# PowerStage.net
KiCad netlist of a schematic drawn in EAGLE
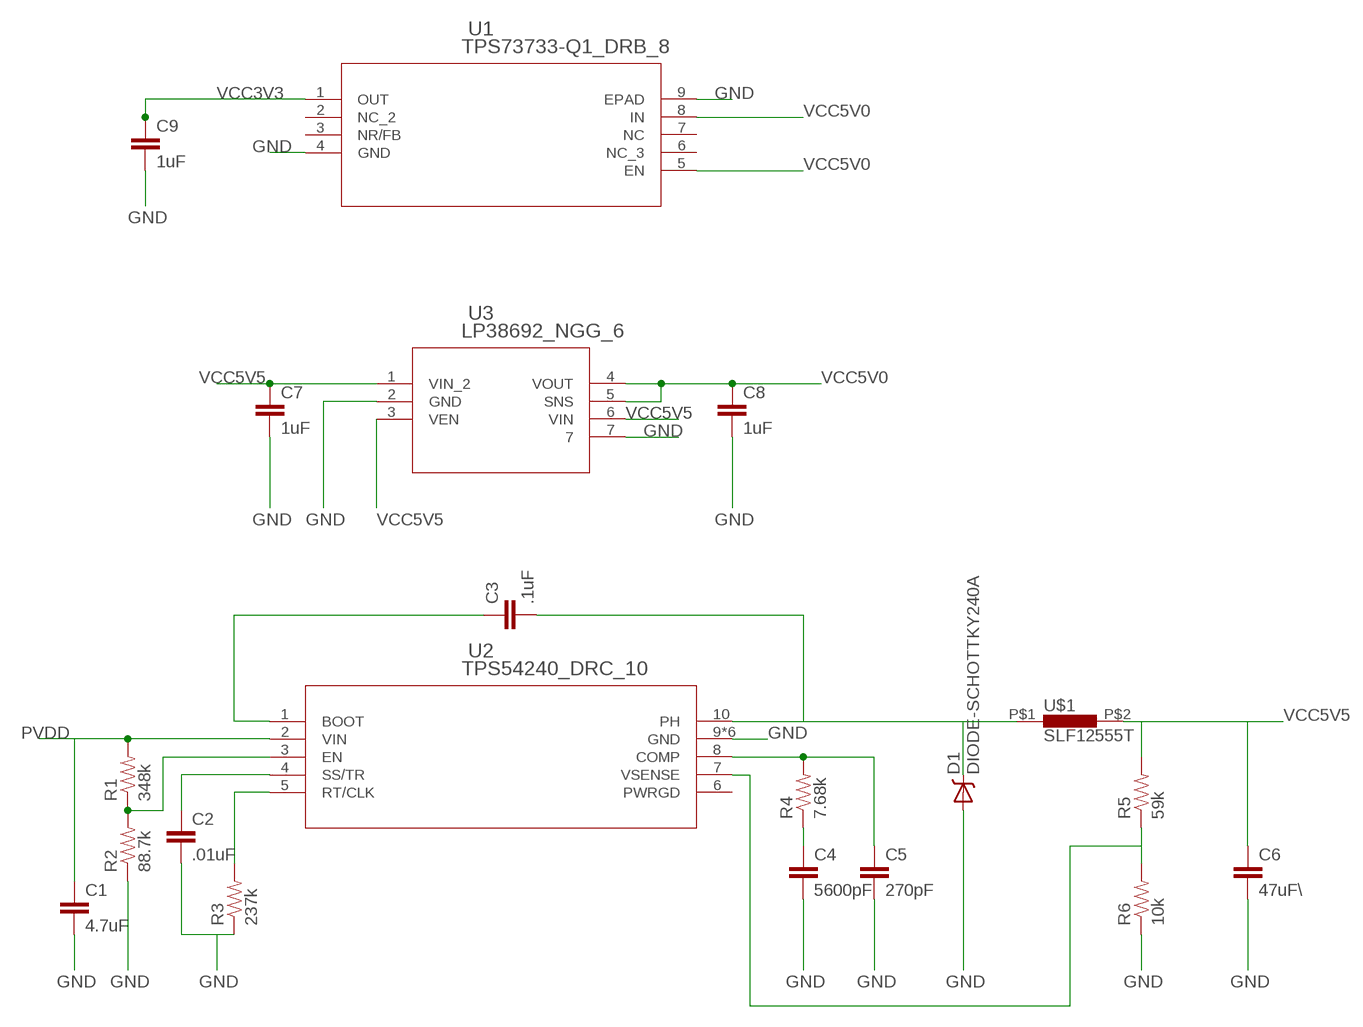
[diagram p0: schematic, sheet 1]

(export (version "E")
  (design (tool "Eeschema 10.0.6"))
  (components
    (comp (ref "C1")
      (value "4.7uF")
      (footprint "eagle-import:1210")
      (libsource (lib "eagle-import") (part "CAP1210"))
    )
    (comp (ref "C2")
      (value ".01uF")
      (footprint "eagle-import:0805")
      (libsource (lib "eagle-import") (part "CAP0805"))
    )
    (comp (ref "C3")
      (value ".1uF")
      (footprint "eagle-import:0805")
      (libsource (lib "eagle-import") (part "CAP0805"))
    )
    (comp (ref "C4")
      (value "5600pF")
      (footprint "eagle-import:0805")
      (libsource (lib "eagle-import") (part "CAP0805"))
    )
    (comp (ref "C5")
      (value "270pF")
      (footprint "eagle-import:0805")
      (libsource (lib "eagle-import") (part "CAP0805"))
    )
    (comp (ref "C6")
      (value "47uF\\")
      (footprint "eagle-import:C2220K")
      (libsource (lib "eagle-import") (part "CAP"))
    )
    (comp (ref "C7")
      (value "1uF")
      (footprint "eagle-import:0805")
      (libsource (lib "eagle-import") (part "CAP0805"))
    )
    (comp (ref "C8")
      (value "1uF")
      (footprint "eagle-import:0805")
      (libsource (lib "eagle-import") (part "CAP0805"))
    )
    (comp (ref "C9")
      (value "1uF")
      (footprint "eagle-import:0805")
      (libsource (lib "eagle-import") (part "CAP0805"))
    )
    (comp (ref "D1")
      (value "DIODE-SCHOTTKY240A")
      (footprint "eagle-import:SMA-DIODE-B240A")
      (libsource (lib "eagle-import") (part "DIODE-SCHOTTKY240A"))
    )
    (comp (ref "R1")
      (value "348k")
      (footprint "eagle-import:0805")
      (libsource (lib "eagle-import") (part "RESISTOR0805-RES"))
    )
    (comp (ref "R2")
      (value "88.7k")
      (footprint "eagle-import:0805")
      (libsource (lib "eagle-import") (part "RESISTOR0805-RES"))
    )
    (comp (ref "R3")
      (value "237k")
      (footprint "eagle-import:0805")
      (libsource (lib "eagle-import") (part "RESISTOR0805-RES"))
    )
    (comp (ref "R4")
      (value "7.68k")
      (footprint "eagle-import:0805")
      (libsource (lib "eagle-import") (part "RESISTOR0805-RES"))
    )
    (comp (ref "R5")
      (value "59k")
      (footprint "eagle-import:0805")
      (libsource (lib "eagle-import") (part "RESISTOR0805-RES"))
    )
    (comp (ref "R6")
      (value "10k")
      (footprint "eagle-import:0805")
      (libsource (lib "eagle-import") (part "RESISTOR0805-RES"))
    )
    (comp (ref "U$1")
      (value "SLF12555T")
      (footprint "eagle-import:SLF12555")
      (libsource (lib "eagle-import") (part "SLF12555T"))
    )
    (comp (ref "U1")
      (value "TPS73733-Q1_DRB_8")
      (footprint "eagle-import:DRB8_1P75X1P5")
      (fields
        (field (name "GENERIC_PART_NUMBER") "TPS73733-Q1")
        (field (name "MANUFACTURER") "Texas Instruments")
        (field (name "MANUFACTURER_PART_NUMBER") "tps73733-q1_drb_8")
      )
      (libsource (lib "eagle-import") (part "TPS73733-Q1_DRB_8"))
    )
    (comp (ref "U2")
      (value "TPS54240_DRC_10")
      (footprint "eagle-import:DRC10_2P4X1P65")
      (fields
        (field (name "GENERIC_PART_NUMBER") "TPS54240")
        (field (name "MANUFACTURER") "Texas Instruments")
        (field (name "MANUFACTURER_PART_NUMBER") "tps54240_drc_10")
      )
      (libsource (lib "eagle-import") (part "TPS54240_DRC_10"))
    )
    (comp (ref "U3")
      (value "LP38692_NGG_6")
      (footprint "eagle-import:SDE06A")
      (fields (field (name "PARTNUMBER") "LP38692SD-18"))
      (libsource (lib "eagle-import") (part "LP38692_NGG_6"))
    )
  )
  (nets
    (net (code "1") (name "/GND") (class "Default")
      (node (ref "C1") (pin "2") (pinfunction "2_2") (pintype "passive"))
      (node (ref "C2") (pin "2") (pinfunction "2_2") (pintype "passive"))
      (node (ref "C4") (pin "2") (pinfunction "2_2") (pintype "passive"))
      (node (ref "C5") (pin "2") (pinfunction "2_2") (pintype "passive"))
      (node (ref "C6") (pin "2") (pinfunction "2_2") (pintype "passive"))
      (node (ref "C7") (pin "2") (pinfunction "2_2") (pintype "passive"))
      (node (ref "C8") (pin "2") (pinfunction "2_2") (pintype "passive"))
      (node (ref "C9") (pin "2") (pinfunction "2_2") (pintype "passive"))
      (node (ref "D1") (pin "A") (pinfunction "A_A") (pintype "passive"))
      (node (ref "R2") (pin "1") (pinfunction "1_1") (pintype "passive"))
      (node (ref "R3") (pin "1") (pinfunction "1_1") (pintype "passive"))
      (node (ref "R6") (pin "1") (pinfunction "1_1") (pintype "passive"))
      (node (ref "U1") (pin "4") (pinfunction "GND_4") (pintype "power_in"))
      (node (ref "U1") (pin "9") (pinfunction "EPAD_9") (pintype "passive"))
      (node (ref "U2") (pin "9") (pinfunction "GND_9") (pintype "power_in"))
      (node (ref "U2") (pin "P$1") (pinfunction "GND_P$1") (pintype "power_in"))
      (node (ref "U2") (pin "P$2") (pinfunction "GND_P$2") (pintype "power_in"))
      (node (ref "U2") (pin "P$3") (pinfunction "GND_P$3") (pintype "power_in"))
      (node (ref "U2") (pin "P$4") (pinfunction "GND_P$4") (pintype "power_in"))
      (node (ref "U2") (pin "P$5") (pinfunction "GND_P$5") (pintype "power_in"))
      (node (ref "U3") (pin "2") (pinfunction "GND_2") (pintype "passive"))
      (node (ref "U3") (pin "7") (pinfunction "7_7") (pintype "passive"))
    )
    (net (code "2") (name "/PVDD") (class "Default")
      (node (ref "C1") (pin "1") (pinfunction "1_1") (pintype "passive"))
      (node (ref "R1") (pin "2") (pinfunction "2_2") (pintype "passive"))
      (node (ref "U2") (pin "2") (pinfunction "VIN_2") (pintype "input"))
    )
    (net (code "3") (name "/VCC3V3") (class "Default")
      (node (ref "C9") (pin "1") (pinfunction "1_1") (pintype "passive"))
      (node (ref "U1") (pin "1") (pinfunction "OUT_1") (pintype "output"))
    )
    (net (code "4") (name "/VCC5V0") (class "Default")
      (node (ref "C8") (pin "1") (pinfunction "1_1") (pintype "passive"))
      (node (ref "U1") (pin "5") (pinfunction "EN_5") (pintype "passive"))
      (node (ref "U1") (pin "8") (pinfunction "IN_8") (pintype "input"))
      (node (ref "U3") (pin "4") (pinfunction "VOUT_4") (pintype "output"))
      (node (ref "U3") (pin "5") (pinfunction "SNS_5") (pintype "passive"))
    )
    (net (code "5") (name "/VCC5V5") (class "Default")
      (node (ref "C6") (pin "1") (pinfunction "1_1") (pintype "passive"))
      (node (ref "C7") (pin "1") (pinfunction "1_1") (pintype "passive"))
      (node (ref "R5") (pin "2") (pinfunction "2_2") (pintype "passive"))
      (node (ref "U$1") (pin "P$2") (pinfunction "2_P$2") (pintype "passive"))
      (node (ref "U3") (pin "1") (pinfunction "VIN_2_1") (pintype "input"))
      (node (ref "U3") (pin "3") (pinfunction "VEN_3") (pintype "passive"))
      (node (ref "U3") (pin "6") (pinfunction "VIN_6") (pintype "input"))
    )
    (net (code "6") (name "Net-(C4-Pad1)") (class "Default")
      (node (ref "C4") (pin "1") (pinfunction "1_1") (pintype "passive"))
      (node (ref "R4") (pin "1") (pinfunction "1_1") (pintype "passive"))
    )
    (net (code "7") (name "Net-(U$1-1)") (class "Default")
      (node (ref "C3") (pin "2") (pinfunction "2_2") (pintype "passive"))
      (node (ref "D1") (pin "C") (pinfunction "C_C") (pintype "passive"))
      (node (ref "U$1") (pin "P$1") (pinfunction "1_P$1") (pintype "passive"))
      (node (ref "U2") (pin "10") (pinfunction "PH_10") (pintype "input"))
    )
    (net (code "8") (name "Net-(U2-BOOT)") (class "Default")
      (node (ref "C3") (pin "1") (pinfunction "1_1") (pintype "passive"))
      (node (ref "U2") (pin "1") (pinfunction "BOOT_1") (pintype "output"))
    )
    (net (code "9") (name "Net-(U2-COMP)") (class "Default")
      (node (ref "C5") (pin "1") (pinfunction "1_1") (pintype "passive"))
      (node (ref "R4") (pin "2") (pinfunction "2_2") (pintype "passive"))
      (node (ref "U2") (pin "8") (pinfunction "COMP_8") (pintype "output"))
    )
    (net (code "10") (name "Net-(U2-EN)") (class "Default")
      (node (ref "R1") (pin "1") (pinfunction "1_1") (pintype "passive"))
      (node (ref "R2") (pin "2") (pinfunction "2_2") (pintype "passive"))
      (node (ref "U2") (pin "3") (pinfunction "EN_3") (pintype "input"))
    )
    (net (code "11") (name "Net-(U2-RT{slash}CLK)") (class "Default")
      (node (ref "R3") (pin "2") (pinfunction "2_2") (pintype "passive"))
      (node (ref "U2") (pin "5") (pinfunction "RT/CLK_5") (pintype "input"))
    )
    (net (code "12") (name "Net-(U2-SS{slash}TR)") (class "Default")
      (node (ref "C2") (pin "1") (pinfunction "1_1") (pintype "passive"))
      (node (ref "U2") (pin "4") (pinfunction "SS/TR_4") (pintype "input"))
    )
    (net (code "13") (name "Net-(U2-VSENSE)") (class "Default")
      (node (ref "R5") (pin "1") (pinfunction "1_1") (pintype "passive"))
      (node (ref "R6") (pin "2") (pinfunction "2_2") (pintype "passive"))
      (node (ref "U2") (pin "7") (pinfunction "VSENSE_7") (pintype "input"))
    )
    (net (code "14") (name "unconnected-(U1-NC-Pad7)") (class "Default")
      (node (ref "U1") (pin "7") (pinfunction "NC_7") (pintype "passive"))
    )
    (net (code "15") (name "unconnected-(U1-NC_2-Pad2)") (class "Default")
      (node (ref "U1") (pin "2") (pinfunction "NC_2_2") (pintype "passive"))
    )
    (net (code "16") (name "unconnected-(U1-NC_3-Pad6)") (class "Default")
      (node (ref "U1") (pin "6") (pinfunction "NC_3_6") (pintype "passive"))
    )
    (net (code "17") (name "unconnected-(U1-NR{slash}FB-Pad3)") (class "Default")
      (node (ref "U1") (pin "3") (pinfunction "NR/FB_3") (pintype "bidirectional"))
    )
    (net (code "18") (name "unconnected-(U2-PWRGD-Pad6)") (class "Default")
      (node (ref "U2") (pin "6") (pinfunction "PWRGD_6") (pintype "output"))
    )
  )
)
